# emitters1.net
KiCad netlist of a schematic drawn in Altium Designer
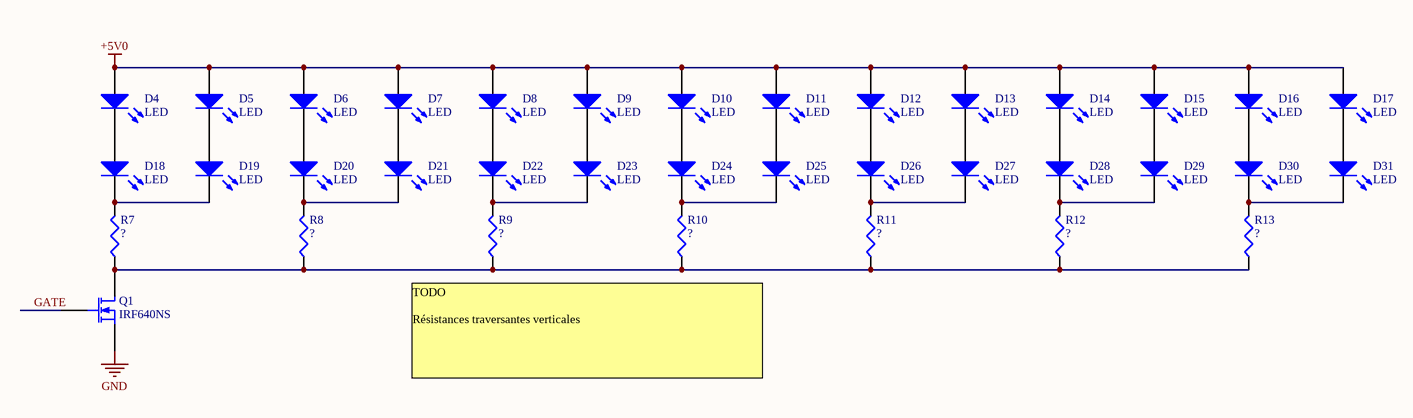
[diagram p0: emitters1.SchDoc]

(export (version "E")
  (design (tool "Eeschema 10.0.6"))
  (components
    (comp (ref "D4")
      (value "LED")
      (footprint "LED 5MM Horiz")
      (description "Typical RED, GREEN, YELLOW, AMBER GaAs LED")
      (fields (field (name "PUBLISHER") "Altium Limited"))
      (libsource (lib "7Robot") (part "LED"))
    )
    (comp (ref "D5")
      (value "LED")
      (footprint "LED 5MM Horiz")
      (description "Typical RED, GREEN, YELLOW, AMBER GaAs LED")
      (fields (field (name "PUBLISHER") "Altium Limited"))
      (libsource (lib "7Robot") (part "LED"))
    )
    (comp (ref "D6")
      (value "LED")
      (footprint "LED 5MM Horiz")
      (description "Typical RED, GREEN, YELLOW, AMBER GaAs LED")
      (fields (field (name "PUBLISHER") "Altium Limited"))
      (libsource (lib "7Robot") (part "LED"))
    )
    (comp (ref "D7")
      (value "LED")
      (footprint "LED 5MM Horiz")
      (description "Typical RED, GREEN, YELLOW, AMBER GaAs LED")
      (fields (field (name "PUBLISHER") "Altium Limited"))
      (libsource (lib "7Robot") (part "LED"))
    )
    (comp (ref "D8")
      (value "LED")
      (footprint "LED 5MM Horiz")
      (description "Typical RED, GREEN, YELLOW, AMBER GaAs LED")
      (fields (field (name "PUBLISHER") "Altium Limited"))
      (libsource (lib "7Robot") (part "LED"))
    )
    (comp (ref "D9")
      (value "LED")
      (footprint "LED 5MM Horiz")
      (description "Typical RED, GREEN, YELLOW, AMBER GaAs LED")
      (fields (field (name "PUBLISHER") "Altium Limited"))
      (libsource (lib "7Robot") (part "LED"))
    )
    (comp (ref "D10")
      (value "LED")
      (footprint "LED 5MM Horiz")
      (description "Typical RED, GREEN, YELLOW, AMBER GaAs LED")
      (fields (field (name "PUBLISHER") "Altium Limited"))
      (libsource (lib "7Robot") (part "LED"))
    )
    (comp (ref "D11")
      (value "LED")
      (footprint "LED 5MM Horiz")
      (description "Typical RED, GREEN, YELLOW, AMBER GaAs LED")
      (fields (field (name "PUBLISHER") "Altium Limited"))
      (libsource (lib "7Robot") (part "LED"))
    )
    (comp (ref "D12")
      (value "LED")
      (footprint "LED 5MM Horiz")
      (description "Typical RED, GREEN, YELLOW, AMBER GaAs LED")
      (fields (field (name "PUBLISHER") "Altium Limited"))
      (libsource (lib "7Robot") (part "LED"))
    )
    (comp (ref "D13")
      (value "LED")
      (footprint "LED 5MM Horiz")
      (description "Typical RED, GREEN, YELLOW, AMBER GaAs LED")
      (fields (field (name "PUBLISHER") "Altium Limited"))
      (libsource (lib "7Robot") (part "LED"))
    )
    (comp (ref "D14")
      (value "LED")
      (footprint "LED 5MM Horiz")
      (description "Typical RED, GREEN, YELLOW, AMBER GaAs LED")
      (fields (field (name "PUBLISHER") "Altium Limited"))
      (libsource (lib "7Robot") (part "LED"))
    )
    (comp (ref "D15")
      (value "LED")
      (footprint "LED 5MM Horiz")
      (description "Typical RED, GREEN, YELLOW, AMBER GaAs LED")
      (fields (field (name "PUBLISHER") "Altium Limited"))
      (libsource (lib "7Robot") (part "LED"))
    )
    (comp (ref "D16")
      (value "LED")
      (footprint "LED 5MM Horiz")
      (description "Typical RED, GREEN, YELLOW, AMBER GaAs LED")
      (fields (field (name "PUBLISHER") "Altium Limited"))
      (libsource (lib "7Robot") (part "LED"))
    )
    (comp (ref "D17")
      (value "LED")
      (footprint "LED 5MM Horiz")
      (description "Typical RED, GREEN, YELLOW, AMBER GaAs LED")
      (fields (field (name "PUBLISHER") "Altium Limited"))
      (libsource (lib "7Robot") (part "LED"))
    )
    (comp (ref "D18")
      (value "LED")
      (footprint "LED 5MM Horiz")
      (description "Typical RED, GREEN, YELLOW, AMBER GaAs LED")
      (fields (field (name "PUBLISHER") "Altium Limited"))
      (libsource (lib "7Robot") (part "LED"))
    )
    (comp (ref "D19")
      (value "LED")
      (footprint "LED 5MM Horiz")
      (description "Typical RED, GREEN, YELLOW, AMBER GaAs LED")
      (fields (field (name "PUBLISHER") "Altium Limited"))
      (libsource (lib "7Robot") (part "LED"))
    )
    (comp (ref "D20")
      (value "LED")
      (footprint "LED 5MM Horiz")
      (description "Typical RED, GREEN, YELLOW, AMBER GaAs LED")
      (fields (field (name "PUBLISHER") "Altium Limited"))
      (libsource (lib "7Robot") (part "LED"))
    )
    (comp (ref "D21")
      (value "LED")
      (footprint "LED 5MM Horiz")
      (description "Typical RED, GREEN, YELLOW, AMBER GaAs LED")
      (fields (field (name "PUBLISHER") "Altium Limited"))
      (libsource (lib "7Robot") (part "LED"))
    )
    (comp (ref "D22")
      (value "LED")
      (footprint "LED 5MM Horiz")
      (description "Typical RED, GREEN, YELLOW, AMBER GaAs LED")
      (fields (field (name "PUBLISHER") "Altium Limited"))
      (libsource (lib "7Robot") (part "LED"))
    )
    (comp (ref "D23")
      (value "LED")
      (footprint "LED 5MM Horiz")
      (description "Typical RED, GREEN, YELLOW, AMBER GaAs LED")
      (fields (field (name "PUBLISHER") "Altium Limited"))
      (libsource (lib "7Robot") (part "LED"))
    )
    (comp (ref "D24")
      (value "LED")
      (footprint "LED 5MM Horiz")
      (description "Typical RED, GREEN, YELLOW, AMBER GaAs LED")
      (fields (field (name "PUBLISHER") "Altium Limited"))
      (libsource (lib "7Robot") (part "LED"))
    )
    (comp (ref "D25")
      (value "LED")
      (footprint "LED 5MM Horiz")
      (description "Typical RED, GREEN, YELLOW, AMBER GaAs LED")
      (fields (field (name "PUBLISHER") "Altium Limited"))
      (libsource (lib "7Robot") (part "LED"))
    )
    (comp (ref "D26")
      (value "LED")
      (footprint "LED 5MM Horiz")
      (description "Typical RED, GREEN, YELLOW, AMBER GaAs LED")
      (fields (field (name "PUBLISHER") "Altium Limited"))
      (libsource (lib "7Robot") (part "LED"))
    )
    (comp (ref "D27")
      (value "LED")
      (footprint "LED 5MM Horiz")
      (description "Typical RED, GREEN, YELLOW, AMBER GaAs LED")
      (fields (field (name "PUBLISHER") "Altium Limited"))
      (libsource (lib "7Robot") (part "LED"))
    )
    (comp (ref "D28")
      (value "LED")
      (footprint "LED 5MM Horiz")
      (description "Typical RED, GREEN, YELLOW, AMBER GaAs LED")
      (fields (field (name "PUBLISHER") "Altium Limited"))
      (libsource (lib "7Robot") (part "LED"))
    )
    (comp (ref "D29")
      (value "LED")
      (footprint "LED 5MM Horiz")
      (description "Typical RED, GREEN, YELLOW, AMBER GaAs LED")
      (fields (field (name "PUBLISHER") "Altium Limited"))
      (libsource (lib "7Robot") (part "LED"))
    )
    (comp (ref "D30")
      (value "LED")
      (footprint "LED 5MM Horiz")
      (description "Typical RED, GREEN, YELLOW, AMBER GaAs LED")
      (fields (field (name "PUBLISHER") "Altium Limited"))
      (libsource (lib "7Robot") (part "LED"))
    )
    (comp (ref "D31")
      (value "LED")
      (footprint "LED 5MM Horiz")
      (description "Typical RED, GREEN, YELLOW, AMBER GaAs LED")
      (fields (field (name "PUBLISHER") "Altium Limited"))
      (libsource (lib "7Robot") (part "LED"))
    )
    (comp (ref "Q1")
      (value "IRF640NS")
      (footprint "D2PAK")
      (description "N-Channel MOSFET, D2PAK (T0-263), InternationalRectifier")
      (fields (field (name "PUBLISHER") "Altium Limited"))
      (libsource (lib "7Robot") (part "IRF640"))
    )
    (comp (ref "R7")
      (value "?")
      (footprint "C0805R")
      (description "Resistor")
      (fields (field (name "Comment") "RES") (field (name "PUBLISHER") "Altium Limited"))
      (libsource (lib "7Robot") (part "RES"))
    )
    (comp (ref "R8")
      (value "?")
      (footprint "C0805R")
      (description "Resistor")
      (fields (field (name "Comment") "RES") (field (name "PUBLISHER") "Altium Limited"))
      (libsource (lib "7Robot") (part "RES"))
    )
    (comp (ref "R9")
      (value "?")
      (footprint "C0805R")
      (description "Resistor")
      (fields (field (name "Comment") "RES") (field (name "PUBLISHER") "Altium Limited"))
      (libsource (lib "7Robot") (part "RES"))
    )
    (comp (ref "R10")
      (value "?")
      (footprint "C0805R")
      (description "Resistor")
      (fields (field (name "Comment") "RES") (field (name "PUBLISHER") "Altium Limited"))
      (libsource (lib "7Robot") (part "RES"))
    )
    (comp (ref "R11")
      (value "?")
      (footprint "C0805R")
      (description "Resistor")
      (fields (field (name "Comment") "RES") (field (name "PUBLISHER") "Altium Limited"))
      (libsource (lib "7Robot") (part "RES"))
    )
    (comp (ref "R12")
      (value "?")
      (footprint "C0805R")
      (description "Resistor")
      (fields (field (name "Comment") "RES") (field (name "PUBLISHER") "Altium Limited"))
      (libsource (lib "7Robot") (part "RES"))
    )
    (comp (ref "R13")
      (value "?")
      (footprint "C0805R")
      (description "Resistor")
      (fields (field (name "Comment") "RES") (field (name "PUBLISHER") "Altium Limited"))
      (libsource (lib "7Robot") (part "RES"))
    )
  )
  (nets
    (net (code "1") (name "+5V0") (class "Default")
      (node (ref "D10") (pin "1") (pinfunction "A_1") (pintype "passive"))
      (node (ref "D11") (pin "1") (pinfunction "A_1") (pintype "passive"))
      (node (ref "D12") (pin "1") (pinfunction "A_1") (pintype "passive"))
      (node (ref "D13") (pin "1") (pinfunction "A_1") (pintype "passive"))
      (node (ref "D14") (pin "1") (pinfunction "A_1") (pintype "passive"))
      (node (ref "D15") (pin "1") (pinfunction "A_1") (pintype "passive"))
      (node (ref "D16") (pin "1") (pinfunction "A_1") (pintype "passive"))
      (node (ref "D17") (pin "1") (pinfunction "A_1") (pintype "passive"))
      (node (ref "D4") (pin "1") (pinfunction "A_1") (pintype "passive"))
      (node (ref "D5") (pin "1") (pinfunction "A_1") (pintype "passive"))
      (node (ref "D6") (pin "1") (pinfunction "A_1") (pintype "passive"))
      (node (ref "D7") (pin "1") (pinfunction "A_1") (pintype "passive"))
      (node (ref "D8") (pin "1") (pinfunction "A_1") (pintype "passive"))
      (node (ref "D9") (pin "1") (pinfunction "A_1") (pintype "passive"))
    )
    (net (code "2") (name "/GATE") (class "Default")
      (node (ref "Q1") (pin "1") (pinfunction "G_1") (pintype "passive"))
    )
    (net (code "3") (name "GND") (class "Default")
      (node (ref "Q1") (pin "3") (pinfunction "S_3") (pintype "passive"))
    )
    (net (code "4") (name "Net-(D10-K)") (class "Default")
      (node (ref "D10") (pin "2") (pinfunction "K_2") (pintype "passive"))
      (node (ref "D24") (pin "1") (pinfunction "A_1") (pintype "passive"))
    )
    (net (code "5") (name "Net-(D11-K)") (class "Default")
      (node (ref "D11") (pin "2") (pinfunction "K_2") (pintype "passive"))
      (node (ref "D25") (pin "1") (pinfunction "A_1") (pintype "passive"))
    )
    (net (code "6") (name "Net-(D12-K)") (class "Default")
      (node (ref "D12") (pin "2") (pinfunction "K_2") (pintype "passive"))
      (node (ref "D26") (pin "1") (pinfunction "A_1") (pintype "passive"))
    )
    (net (code "7") (name "Net-(D13-K)") (class "Default")
      (node (ref "D13") (pin "2") (pinfunction "K_2") (pintype "passive"))
      (node (ref "D27") (pin "1") (pinfunction "A_1") (pintype "passive"))
    )
    (net (code "8") (name "Net-(D14-K)") (class "Default")
      (node (ref "D14") (pin "2") (pinfunction "K_2") (pintype "passive"))
      (node (ref "D28") (pin "1") (pinfunction "A_1") (pintype "passive"))
    )
    (net (code "9") (name "Net-(D15-K)") (class "Default")
      (node (ref "D15") (pin "2") (pinfunction "K_2") (pintype "passive"))
      (node (ref "D29") (pin "1") (pinfunction "A_1") (pintype "passive"))
    )
    (net (code "10") (name "Net-(D16-K)") (class "Default")
      (node (ref "D16") (pin "2") (pinfunction "K_2") (pintype "passive"))
      (node (ref "D30") (pin "1") (pinfunction "A_1") (pintype "passive"))
    )
    (net (code "11") (name "Net-(D17-K)") (class "Default")
      (node (ref "D17") (pin "2") (pinfunction "K_2") (pintype "passive"))
      (node (ref "D31") (pin "1") (pinfunction "A_1") (pintype "passive"))
    )
    (net (code "12") (name "Net-(D18-A)") (class "Default")
      (node (ref "D18") (pin "1") (pinfunction "A_1") (pintype "passive"))
      (node (ref "D4") (pin "2") (pinfunction "K_2") (pintype "passive"))
    )
    (net (code "13") (name "Net-(D18-K)") (class "Default")
      (node (ref "D18") (pin "2") (pinfunction "K_2") (pintype "passive"))
      (node (ref "D19") (pin "2") (pinfunction "K_2") (pintype "passive"))
      (node (ref "R7") (pin "2") (pinfunction "2_2") (pintype "passive"))
    )
    (net (code "14") (name "Net-(D19-A)") (class "Default")
      (node (ref "D19") (pin "1") (pinfunction "A_1") (pintype "passive"))
      (node (ref "D5") (pin "2") (pinfunction "K_2") (pintype "passive"))
    )
    (net (code "15") (name "Net-(D20-A)") (class "Default")
      (node (ref "D20") (pin "1") (pinfunction "A_1") (pintype "passive"))
      (node (ref "D6") (pin "2") (pinfunction "K_2") (pintype "passive"))
    )
    (net (code "16") (name "Net-(D20-K)") (class "Default")
      (node (ref "D20") (pin "2") (pinfunction "K_2") (pintype "passive"))
      (node (ref "D21") (pin "2") (pinfunction "K_2") (pintype "passive"))
      (node (ref "R8") (pin "2") (pinfunction "2_2") (pintype "passive"))
    )
    (net (code "17") (name "Net-(D21-A)") (class "Default")
      (node (ref "D21") (pin "1") (pinfunction "A_1") (pintype "passive"))
      (node (ref "D7") (pin "2") (pinfunction "K_2") (pintype "passive"))
    )
    (net (code "18") (name "Net-(D22-A)") (class "Default")
      (node (ref "D22") (pin "1") (pinfunction "A_1") (pintype "passive"))
      (node (ref "D8") (pin "2") (pinfunction "K_2") (pintype "passive"))
    )
    (net (code "19") (name "Net-(D22-K)") (class "Default")
      (node (ref "D22") (pin "2") (pinfunction "K_2") (pintype "passive"))
      (node (ref "D23") (pin "2") (pinfunction "K_2") (pintype "passive"))
      (node (ref "R9") (pin "2") (pinfunction "2_2") (pintype "passive"))
    )
    (net (code "20") (name "Net-(D23-A)") (class "Default")
      (node (ref "D23") (pin "1") (pinfunction "A_1") (pintype "passive"))
      (node (ref "D9") (pin "2") (pinfunction "K_2") (pintype "passive"))
    )
    (net (code "21") (name "Net-(D24-K)") (class "Default")
      (node (ref "D24") (pin "2") (pinfunction "K_2") (pintype "passive"))
      (node (ref "D25") (pin "2") (pinfunction "K_2") (pintype "passive"))
      (node (ref "R10") (pin "2") (pinfunction "2_2") (pintype "passive"))
    )
    (net (code "22") (name "Net-(D26-K)") (class "Default")
      (node (ref "D26") (pin "2") (pinfunction "K_2") (pintype "passive"))
      (node (ref "D27") (pin "2") (pinfunction "K_2") (pintype "passive"))
      (node (ref "R11") (pin "2") (pinfunction "2_2") (pintype "passive"))
    )
    (net (code "23") (name "Net-(D28-K)") (class "Default")
      (node (ref "D28") (pin "2") (pinfunction "K_2") (pintype "passive"))
      (node (ref "D29") (pin "2") (pinfunction "K_2") (pintype "passive"))
      (node (ref "R12") (pin "2") (pinfunction "2_2") (pintype "passive"))
    )
    (net (code "24") (name "Net-(D30-K)") (class "Default")
      (node (ref "D30") (pin "2") (pinfunction "K_2") (pintype "passive"))
      (node (ref "D31") (pin "2") (pinfunction "K_2") (pintype "passive"))
      (node (ref "R13") (pin "2") (pinfunction "2_2") (pintype "passive"))
    )
    (net (code "25") (name "Net-(Q1-D)") (class "Default")
      (node (ref "Q1") (pin "2") (pinfunction "D_2") (pintype "passive"))
      (node (ref "R10") (pin "1") (pinfunction "1_1") (pintype "passive"))
      (node (ref "R11") (pin "1") (pinfunction "1_1") (pintype "passive"))
      (node (ref "R12") (pin "1") (pinfunction "1_1") (pintype "passive"))
      (node (ref "R13") (pin "1") (pinfunction "1_1") (pintype "passive"))
      (node (ref "R7") (pin "1") (pinfunction "1_1") (pintype "passive"))
      (node (ref "R8") (pin "1") (pinfunction "1_1") (pintype "passive"))
      (node (ref "R9") (pin "1") (pinfunction "1_1") (pintype "passive"))
    )
  )
)
